# Power.net
KiCad netlist of a schematic drawn in Altium Designer
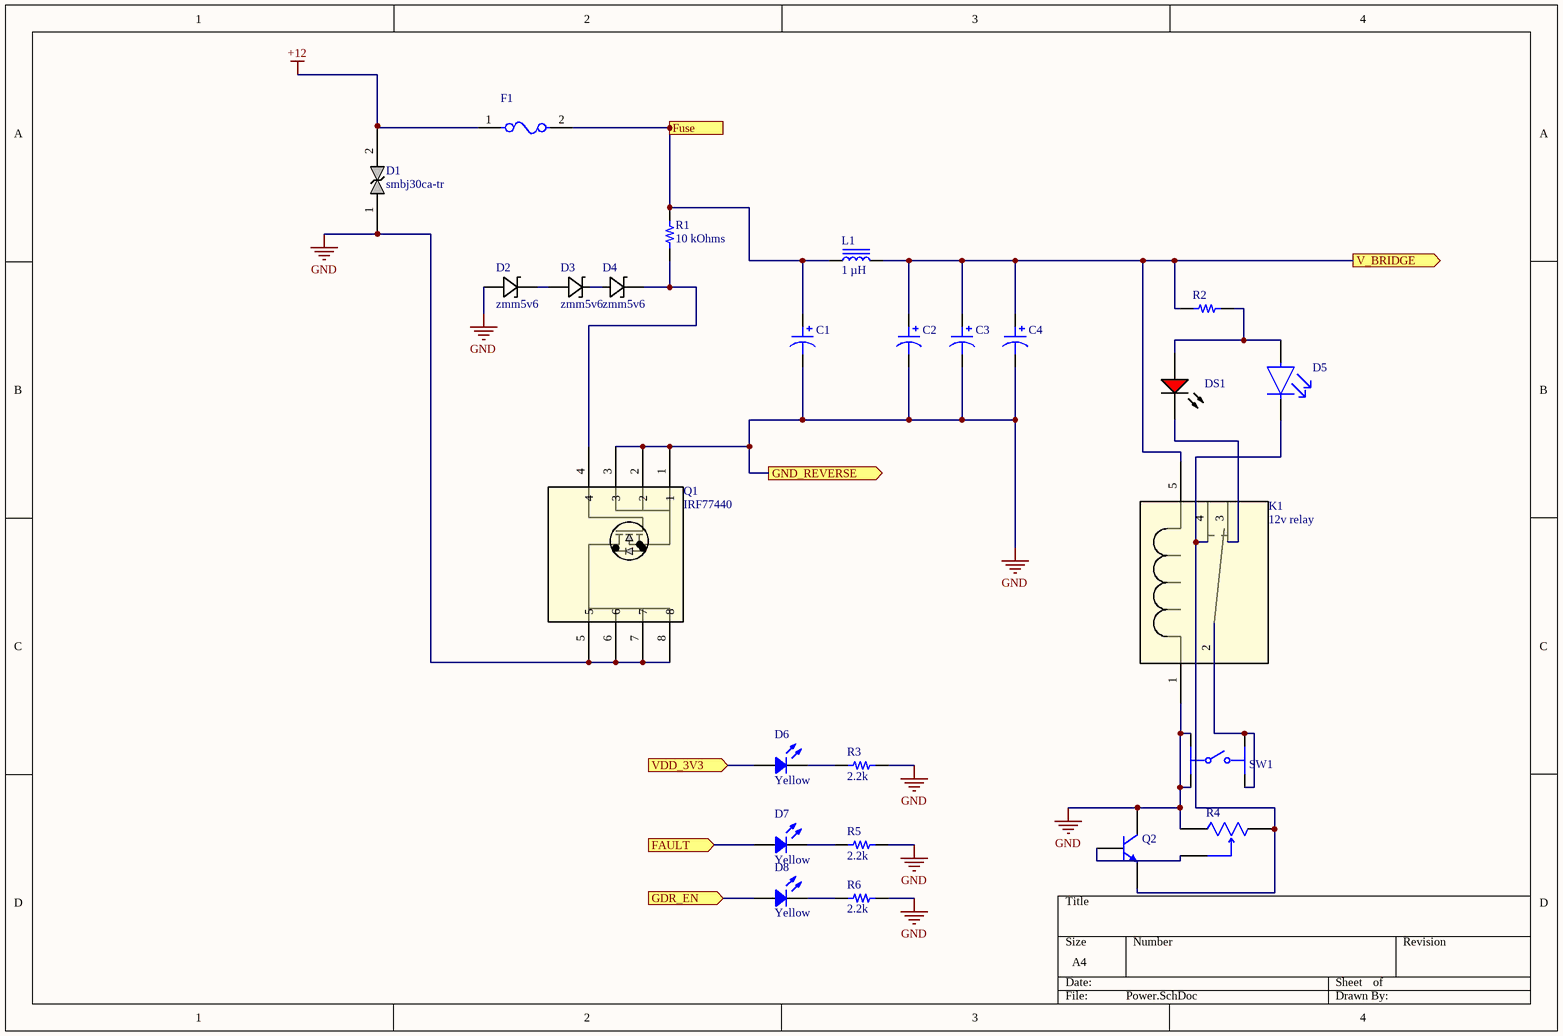
[diagram p0: Power.SchDoc]

(export (version "E")
  (design (tool "Eeschema 10.0.6"))
  (components
    (comp (ref "C1")
      (value "100 µF")
      (footprint "CAP POL 1411_3528")
      (description "CAP TANT 100UF 20% 6.3V 1411")
      (fields (field (name "PART NUMBER") "T495B107M006ATE700") (field (name "MANUFACTURER") "KEMET"))
      (libsource (lib "Celestial Altium Library - altium_library (4)") (part "Polarised Capacitor"))
    )
    (comp (ref "C2")
      (value "100 µF")
      (footprint "CAP POL 1411_3528")
      (description "CAP TANT 100UF 20% 6.3V 1411")
      (fields (field (name "PART NUMBER") "T495B107M006ATE700") (field (name "MANUFACTURER") "KEMET"))
      (libsource (lib "Celestial Altium Library - altium_library (4)") (part "Polarised Capacitor"))
    )
    (comp (ref "C3")
      (value "100 µF")
      (footprint "CAP POL 1411_3528")
      (description "CAP TANT 100UF 20% 6.3V 1411")
      (fields (field (name "PART NUMBER") "T495B107M006ATE700") (field (name "MANUFACTURER") "KEMET"))
      (libsource (lib "Celestial Altium Library - altium_library (4)") (part "Polarised Capacitor"))
    )
    (comp (ref "C4")
      (value "100 µF")
      (footprint "CAP POL 1411_3528")
      (description "CAP TANT 100UF 20% 6.3V 1411")
      (fields (field (name "PART NUMBER") "T495B107M006ATE700") (field (name "MANUFACTURER") "KEMET"))
      (libsource (lib "Celestial Altium Library - altium_library (4)") (part "Polarised Capacitor"))
    )
    (comp (ref "D1")
      (value "smbj30ca-tr")
      (footprint "smbj30ca-tr")
      (libsource (lib "Schlib1") (part "smbj30ca-tr"))
    )
    (comp (ref "D2") (value "zmm5v6") (footprint "zmm5v6") (libsource (lib "Schlib1") (part "zmm5v6")))
    (comp (ref "D3") (value "zmm5v6") (footprint "zmm5v6") (libsource (lib "Schlib1") (part "zmm5v6")))
    (comp (ref "D4") (value "zmm5v6") (footprint "zmm5v6") (libsource (lib "Schlib1") (part "zmm5v6")))
    (comp (ref "D5")
      (value "LTST-C190GKT")
      (footprint "FP-LTST-C190GKT-MFG")
      (description "LED GREEN CLEAR CHIP SMD")
      (fields (field (name "VOLTAGE") "2V"))
      (libsource (lib "Altium Content Vault") (part "8706943c75ba83719d021d2fdc84c58"))
    )
    (comp (ref "D6")
      (value "Yellow")
      (footprint "LED 0402_1005 YELLOW")
      (description "SM LED 0402 YEL 590NM")
      (fields (field (name "PART NUMBER") "5988A40107F") (field (name "MANUFACTURER") "Dialight"))
      (libsource (lib "Celestial Altium Library - altium_library (4)") (part "LED"))
    )
    (comp (ref "D7")
      (value "Yellow")
      (footprint "LED 0402_1005 YELLOW")
      (description "SM LED 0402 YEL 590NM")
      (fields (field (name "PART NUMBER") "5988A40107F") (field (name "MANUFACTURER") "Dialight"))
      (libsource (lib "Celestial Altium Library - altium_library (4)") (part "LED"))
    )
    (comp (ref "D8")
      (value "Yellow")
      (footprint "LED 0402_1005 YELLOW")
      (description "SM LED 0402 YEL 590NM")
      (fields (field (name "PART NUMBER") "5988A40107F") (field (name "MANUFACTURER") "Dialight"))
      (libsource (lib "Celestial Altium Library - altium_library (4)") (part "LED"))
    )
    (comp (ref "DS1")
      (value "TLMS1100-GS08")
      (footprint "VISH-TLMX1100_V")
      (description "LED, RED, 2.1 V, -40 to 100 degC, 2-Pin SMD (0603), RoHS, Tape and Reel")
      (fields (field (name "TOLERANCE") "5%"))
      (libsource (lib "Altium Content Vault") (part "LED-RED-AK-2"))
    )
    (comp (ref "F1")
      (value "SF-2923UC60C-2")
      (footprint "FP-SF-2923-MFG")
      (description "SINGLFUSE 2923 ULTRA-HIGH-I 80VD")
      (fields
        (field (name "MANUFACTURER") "Bourns")
        (field (name "OCTOPART") "https://octopart.com/sf-2923uc60c-2-bourns-98542147")
      )
      (libsource (lib "Altium Content Vault") (part "5bcf9b9f640e542cf0359d10258e979"))
    )
    (comp (ref "K1")
      (value "12v relay")
      (footprint "12V relay")
      (libsource (lib "Schlib1") (part "12v relay"))
    )
    (comp (ref "L1")
      (value "1 µH")
      (footprint "WURTH WE-HCI 7040")
      (description "FIXED IND 1UH 15A 4.6 MOHM SMD")
      (fields (field (name "PART NUMBER") "744311100") (field (name "MANUFACTURER") "Würth Elektronik"))
      (libsource (lib "Celestial Altium Library - altium_library (4)") (part "Inductor"))
    )
    (comp (ref "Q1") (value "IRF77440") (footprint "IRF77440") (libsource (lib "Schlib1") (part "IRF77440")))
    (comp (ref "Q2")
      (value "BC547B")
      (footprint "ONSC-TO-92-3-29-11")
      (description "Amplifier Transistor, NPN Silicon, 3-Pin TO-92, Bulk Box")
      (fields (field (name "MANUFACTURER") "On Semiconductor"))
      (libsource (lib "Altium Content Vault") (part "ONSC-NPN-C1B2E3-3"))
    )
    (comp (ref "R1")
      (value "10 kOhms")
      (footprint "RES 0603_1608")
      (description "RES0603 1% 10K OHM")
      (fields
        (field (name "PART NUMBER") "RM06F1002CT")
        (field (name "MANUFACTURER") "Cal-Chip Electronics, Inc.")
      )
      (libsource (lib "Celestial Altium Library - altium_library (4)") (part "Resistor"))
    )
    (comp (ref "R2")
      (value "1 kOhms")
      (footprint "RES 1206_3216")
      (description "RES 1K OHM 1% 1/2W 1206")
      (fields
        (field (name "PART NUMBER") "RNCP1206FTD1K00")
        (field (name "MANUFACTURER") "Stackpole Electronics Inc")
      )
      (libsource (lib "Celestial Altium Library - altium_library (4)") (part "Resistor"))
    )
    (comp (ref "R3")
      (value "2.2k")
      (footprint "RES 0603_1608")
      (description "RES0603 1% 10K OHM")
      (fields
        (field (name "PART NUMBER") "RM06F1002CT")
        (field (name "MANUFACTURER") "Cal-Chip Electronics, Inc.")
      )
      (libsource (lib "Celestial Altium Library - altium_library (4)") (part "Resistor"))
    )
    (comp (ref "R4")
      (value "TS53YJ104MR10")
      (footprint "FP-TS53YJ-MFG")
      (description "TRIMMER 100KOHM 0.25W J LEAD TOP")
      (fields (field (name "TOLERANCE") "20%"))
      (libsource (lib "Altium Content Vault") (part "fba7ace652dc9f73499b871a67eb50e"))
    )
    (comp (ref "R5")
      (value "2.2k")
      (footprint "RES 0603_1608")
      (description "RES0603 1% 10K OHM")
      (fields
        (field (name "PART NUMBER") "RM06F1002CT")
        (field (name "MANUFACTURER") "Cal-Chip Electronics, Inc.")
      )
      (libsource (lib "Celestial Altium Library - altium_library (4)") (part "Resistor"))
    )
    (comp (ref "R6")
      (value "2.2k")
      (footprint "RES 0603_1608")
      (description "RES0603 1% 10K OHM")
      (fields
        (field (name "PART NUMBER") "RM06F1002CT")
        (field (name "MANUFACTURER") "Cal-Chip Electronics, Inc.")
      )
      (libsource (lib "Celestial Altium Library - altium_library (4)") (part "Resistor"))
    )
    (comp (ref "SW1")
      (value "3-1825910-1")
      (footprint "FP-3-1825910-1-MFG")
      (description "SWITCH TACTILE SPST-NO 0.05A 24V")
      (fields
        (field (name "MANUFACTURER") "TE Connectivity")
        (field (name "OCTOPART") "https://octopart.com/3-1825910-1-te+connectivity-46506874")
      )
      (libsource (lib "Altium Content Vault") (part "b8895f3f4cefb76e1819d2863dba89b"))
    )
  )
  (nets
    (net (code "1") (name "+12") (class "Default")
      (node (ref "D1") (pin "2") (pinfunction "2_2") (pintype "passive"))
      (node (ref "F1") (pin "1") (pinfunction "1_1") (pintype "passive"))
    )
    (net (code "2") (name "/FAULT") (class "Default")
      (node (ref "D7") (pin "1") (pinfunction "1_1") (pintype "passive"))
    )
    (net (code "3") (name "/Fuse") (class "Default")
      (node (ref "C1") (pin "1") (pinfunction "1_1") (pintype "passive"))
      (node (ref "F1") (pin "2") (pinfunction "2_2") (pintype "passive"))
      (node (ref "L1") (pin "1") (pinfunction "1_1") (pintype "passive"))
      (node (ref "R1") (pin "2") (pinfunction "2_2") (pintype "passive"))
    )
    (net (code "4") (name "/GDR_EN") (class "Default")
      (node (ref "D8") (pin "1") (pinfunction "1_1") (pintype "passive"))
    )
    (net (code "5") (name "/VDD_3V3") (class "Default")
      (node (ref "D6") (pin "1") (pinfunction "1_1") (pintype "passive"))
    )
    (net (code "6") (name "/V_BRIDGE") (class "Default")
      (node (ref "C2") (pin "1") (pinfunction "1_1") (pintype "passive"))
      (node (ref "C3") (pin "1") (pinfunction "1_1") (pintype "passive"))
      (node (ref "C4") (pin "1") (pinfunction "1_1") (pintype "passive"))
      (node (ref "K1") (pin "5") (pinfunction "5_5") (pintype "passive"))
      (node (ref "L1") (pin "2") (pinfunction "2_2") (pintype "passive"))
      (node (ref "R2") (pin "2") (pinfunction "2_2") (pintype "passive"))
    )
    (net (code "7") (name "GND") (class "Default")
      (node (ref "C1") (pin "2") (pinfunction "2_2") (pintype "passive"))
      (node (ref "C2") (pin "2") (pinfunction "2_2") (pintype "passive"))
      (node (ref "C3") (pin "2") (pinfunction "2_2") (pintype "passive"))
      (node (ref "C4") (pin "2") (pinfunction "2_2") (pintype "passive"))
      (node (ref "D1") (pin "1") (pinfunction "1_1") (pintype "passive"))
      (node (ref "D2") (pin "2") (pinfunction "ANODE_2") (pintype "passive"))
      (node (ref "K1") (pin "1") (pinfunction "1_1") (pintype "passive"))
      (node (ref "Q1") (pin "1") (pinfunction "1_1") (pintype "passive"))
      (node (ref "Q1") (pin "2") (pinfunction "2_2") (pintype "passive"))
      (node (ref "Q1") (pin "3") (pinfunction "3_3") (pintype "passive"))
      (node (ref "Q1") (pin "5") (pinfunction "5_5") (pintype "passive"))
      (node (ref "Q1") (pin "6") (pinfunction "6_6") (pintype "passive"))
      (node (ref "Q1") (pin "7") (pinfunction "7_7") (pintype "passive"))
      (node (ref "Q1") (pin "8") (pinfunction "8_8") (pintype "passive"))
      (node (ref "Q2") (pin "1") (pinfunction "C_1") (pintype "passive"))
      (node (ref "R3") (pin "1") (pinfunction "1_1") (pintype "passive"))
      (node (ref "R4") (pin "1") (pinfunction "a_1") (pintype "passive"))
      (node (ref "R5") (pin "1") (pinfunction "1_1") (pintype "passive"))
      (node (ref "R6") (pin "1") (pinfunction "1_1") (pintype "passive"))
      (node (ref "SW1") (pin "1") (pinfunction "1_1") (pintype "passive"))
      (node (ref "SW1") (pin "2") (pinfunction "2_2") (pintype "passive"))
    )
    (net (code "8") (name "Net-(D2-CATHODE)") (class "Default")
      (node (ref "D2") (pin "1") (pinfunction "CATHODE_1") (pintype "passive"))
      (node (ref "D3") (pin "2") (pinfunction "ANODE_2") (pintype "passive"))
    )
    (net (code "9") (name "Net-(D3-CATHODE)") (class "Default")
      (node (ref "D3") (pin "1") (pinfunction "CATHODE_1") (pintype "passive"))
      (node (ref "D4") (pin "2") (pinfunction "ANODE_2") (pintype "passive"))
    )
    (net (code "10") (name "Net-(D4-CATHODE)") (class "Default")
      (node (ref "D4") (pin "1") (pinfunction "CATHODE_1") (pintype "passive"))
      (node (ref "Q1") (pin "4") (pinfunction "4_4") (pintype "passive"))
      (node (ref "R1") (pin "1") (pinfunction "1_1") (pintype "passive"))
    )
    (net (code "11") (name "Net-(D5-A)") (class "Default")
      (node (ref "D5") (pin "2") (pinfunction "A_2") (pintype "passive"))
      (node (ref "DS1") (pin "1") (pinfunction "A_1") (pintype "passive"))
      (node (ref "R2") (pin "1") (pinfunction "1_1") (pintype "passive"))
    )
    (net (code "12") (name "Net-(D5-C)") (class "Default")
      (node (ref "D5") (pin "1") (pinfunction "C_1") (pintype "passive"))
      (node (ref "K1") (pin "4") (pinfunction "4_4") (pintype "passive"))
      (node (ref "Q2") (pin "3") (pinfunction "E_3") (pintype "passive"))
      (node (ref "R4") (pin "3") (pinfunction "c_3") (pintype "passive"))
    )
    (net (code "13") (name "Net-(D6-Pad2)") (class "Default")
      (node (ref "D6") (pin "2") (pinfunction "2_2") (pintype "passive"))
      (node (ref "R3") (pin "2") (pinfunction "2_2") (pintype "passive"))
    )
    (net (code "14") (name "Net-(D7-Pad2)") (class "Default")
      (node (ref "D7") (pin "2") (pinfunction "2_2") (pintype "passive"))
      (node (ref "R5") (pin "2") (pinfunction "2_2") (pintype "passive"))
    )
    (net (code "15") (name "Net-(D8-Pad2)") (class "Default")
      (node (ref "D8") (pin "2") (pinfunction "2_2") (pintype "passive"))
      (node (ref "R6") (pin "2") (pinfunction "2_2") (pintype "passive"))
    )
    (net (code "16") (name "Net-(DS1-K)") (class "Default")
      (node (ref "DS1") (pin "2") (pinfunction "K_2") (pintype "passive"))
      (node (ref "K1") (pin "3") (pinfunction "3_3") (pintype "passive"))
    )
    (net (code "17") (name "Net-(K1-Pad2)") (class "Default")
      (node (ref "K1") (pin "2") (pinfunction "2_2") (pintype "passive"))
      (node (ref "SW1") (pin "3") (pinfunction "3_3") (pintype "passive"))
      (node (ref "SW1") (pin "4") (pinfunction "4_4") (pintype "passive"))
    )
    (net (code "18") (name "Net-(Q2-B)") (class "Default")
      (node (ref "Q2") (pin "2") (pinfunction "B_2") (pintype "passive"))
      (node (ref "R4") (pin "2") (pinfunction "b_2") (pintype "passive"))
    )
  )
)
